# vusb_version.net
KiCad netlist of a schematic drawn in EAGLE
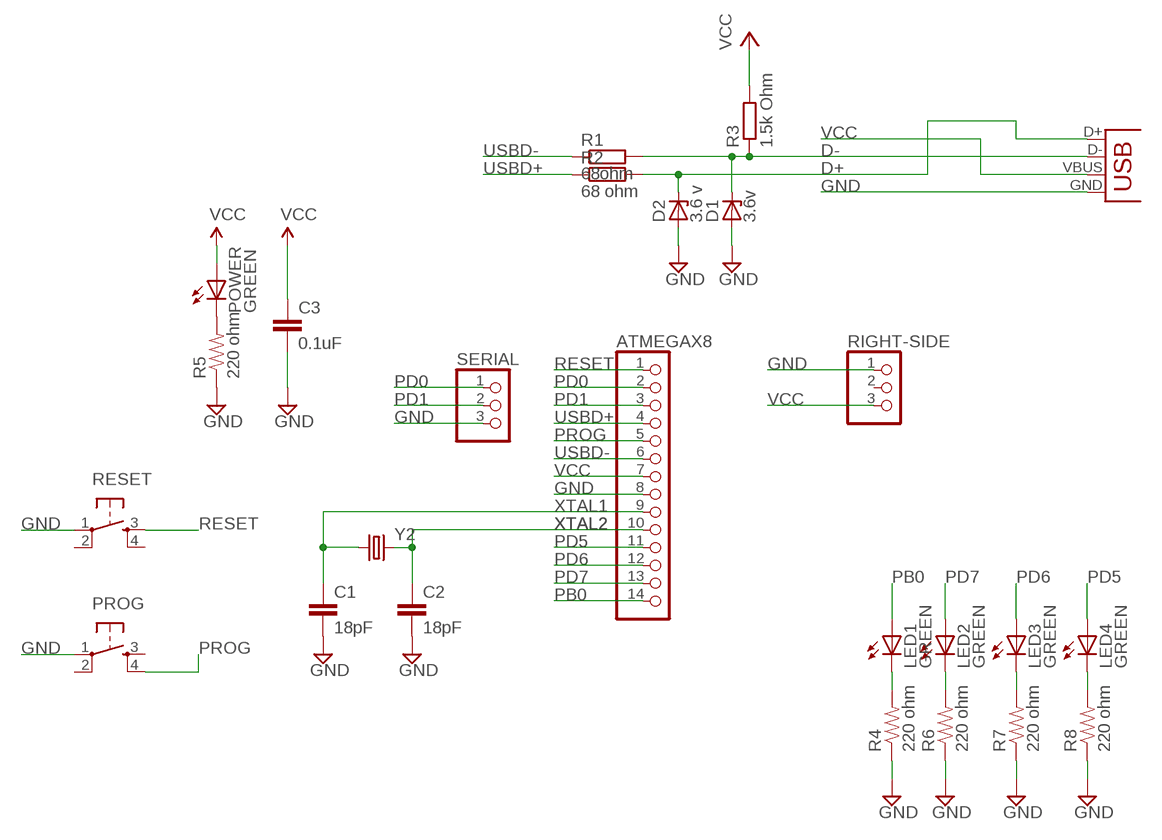
[diagram p0: schematic, sheet 1]

(export (version "E")
  (design (tool "Eeschema 10.0.6"))
  (components
    (comp (ref "ATMEGAX8")
      (value "PINHD-1X14")
      (footprint "eagle-import:1X14")
      (libsource (lib "eagle-import") (part "PINHD-1X14"))
    )
    (comp (ref "C1")
      (value "18pF")
      (footprint "eagle-import:1206")
      (libsource (lib "eagle-import") (part "CAP1206"))
    )
    (comp (ref "C2")
      (value "18pF")
      (footprint "eagle-import:1206")
      (libsource (lib "eagle-import") (part "CAP1206"))
    )
    (comp (ref "C3")
      (value "0.1uF")
      (footprint "eagle-import:1206")
      (libsource (lib "eagle-import") (part "CAP1206"))
    )
    (comp (ref "D1")
      (value "3.6v")
      (footprint "eagle-import:SOT23")
      (libsource (lib "eagle-import") (part "ZENER-DIODESOT23"))
    )
    (comp (ref "D2")
      (value "3.6 v")
      (footprint "eagle-import:SOT23")
      (libsource (lib "eagle-import") (part "ZENER-DIODESOT23"))
    )
    (comp (ref "JP1")
      (value "USBSMD")
      (footprint "eagle-import:USB-MINIB")
      (libsource (lib "eagle-import") (part "USBSMD"))
    )
    (comp (ref "LED1")
      (value "GREEN")
      (footprint "eagle-import:LED-1206")
      (libsource (lib "eagle-import") (part "LED-GREENLARGE"))
    )
    (comp (ref "LED2")
      (value "GREEN")
      (footprint "eagle-import:LED-1206")
      (libsource (lib "eagle-import") (part "LED-GREENLARGE"))
    )
    (comp (ref "LED3")
      (value "GREEN")
      (footprint "eagle-import:LED-1206")
      (libsource (lib "eagle-import") (part "LED-GREENLARGE"))
    )
    (comp (ref "LED4")
      (value "GREEN")
      (footprint "eagle-import:LED-1206")
      (libsource (lib "eagle-import") (part "LED-GREENLARGE"))
    )
    (comp (ref "POWER")
      (value "GREEN")
      (footprint "eagle-import:LED-1206")
      (libsource (lib "eagle-import") (part "LED-GREENLARGE"))
    )
    (comp (ref "PROG")
      (value "TAC_SWITCHPTH")
      (footprint "eagle-import:TACTILE-PTH")
      (libsource (lib "eagle-import") (part "TAC_SWITCHPTH"))
    )
    (comp (ref "R1")
      (value "68ohm")
      (footprint "eagle-import:R0805")
      (libsource (lib "eagle-import") (part "R-EU_R0805"))
    )
    (comp (ref "R2")
      (value "68 ohm")
      (footprint "eagle-import:R0805")
      (libsource (lib "eagle-import") (part "R-EU_R0805"))
    )
    (comp (ref "R3")
      (value "1.5k Ohm")
      (footprint "eagle-import:R1206")
      (libsource (lib "eagle-import") (part "R-EU_R1206"))
    )
    (comp (ref "R4")
      (value "220 ohm")
      (footprint "eagle-import:1206")
      (libsource (lib "eagle-import") (part "RESISTOR1206"))
    )
    (comp (ref "R5")
      (value "220 ohm")
      (footprint "eagle-import:1206")
      (libsource (lib "eagle-import") (part "RESISTOR1206"))
    )
    (comp (ref "R6")
      (value "220 ohm")
      (footprint "eagle-import:1206")
      (libsource (lib "eagle-import") (part "RESISTOR1206"))
    )
    (comp (ref "R7")
      (value "220 ohm")
      (footprint "eagle-import:1206")
      (libsource (lib "eagle-import") (part "RESISTOR1206"))
    )
    (comp (ref "R8")
      (value "220 ohm")
      (footprint "eagle-import:1206")
      (libsource (lib "eagle-import") (part "RESISTOR1206"))
    )
    (comp (ref "RESET")
      (value "TAC_SWITCHPTH")
      (footprint "eagle-import:TACTILE-PTH")
      (libsource (lib "eagle-import") (part "TAC_SWITCHPTH"))
    )
    (comp (ref "RIGHT-SIDE")
      (value "PINHD-1X3")
      (footprint "eagle-import:1X03")
      (libsource (lib "eagle-import") (part "PINHD-1X3"))
    )
    (comp (ref "SERIAL")
      (value "PINHD-1X3")
      (footprint "eagle-import:1X03")
      (libsource (lib "eagle-import") (part "PINHD-1X3"))
    )
    (comp (ref "Y2")
      (value "CRYSTALHC49US")
      (footprint "eagle-import:HC49US")
      (libsource (lib "eagle-import") (part "CRYSTALHC49US"))
    )
  )
  (nets
    (net (code "1") (name "/D+") (class "Default")
      (node (ref "D2") (pin "3") (pinfunction "C_3") (pintype "passive"))
      (node (ref "JP1") (pin "D+") (pinfunction "D+_D+") (pintype "bidirectional"))
      (node (ref "R2") (pin "2") (pinfunction "2_2") (pintype "passive"))
    )
    (net (code "2") (name "/D-") (class "Default")
      (node (ref "D1") (pin "3") (pinfunction "C_3") (pintype "passive"))
      (node (ref "JP1") (pin "D-") (pinfunction "D-_D-") (pintype "bidirectional"))
      (node (ref "R1") (pin "2") (pinfunction "2_2") (pintype "passive"))
      (node (ref "R3") (pin "1") (pinfunction "1_1") (pintype "passive"))
    )
    (net (code "3") (name "/PB0") (class "Default")
      (node (ref "LED1") (pin "A") (pinfunction "A_A") (pintype "passive"))
    )
    (net (code "4") (name "/PD0") (class "Default")
      (node (ref "ATMEGAX8") (pin "2") (pinfunction "2_2") (pintype "passive"))
      (node (ref "SERIAL") (pin "1") (pinfunction "1_1") (pintype "passive"))
    )
    (net (code "5") (name "/PD1") (class "Default")
      (node (ref "ATMEGAX8") (pin "3") (pinfunction "3_3") (pintype "passive"))
      (node (ref "SERIAL") (pin "2") (pinfunction "2_2") (pintype "passive"))
    )
    (net (code "6") (name "/PD5") (class "Default")
      (node (ref "ATMEGAX8") (pin "11") (pinfunction "11_11") (pintype "passive"))
      (node (ref "LED4") (pin "A") (pinfunction "A_A") (pintype "passive"))
    )
    (net (code "7") (name "/PD6") (class "Default")
      (node (ref "ATMEGAX8") (pin "12") (pinfunction "12_12") (pintype "passive"))
      (node (ref "LED3") (pin "A") (pinfunction "A_A") (pintype "passive"))
    )
    (net (code "8") (name "/PD7") (class "Default")
      (node (ref "ATMEGAX8") (pin "13") (pinfunction "13_13") (pintype "passive"))
      (node (ref "LED2") (pin "A") (pinfunction "A_A") (pintype "passive"))
    )
    (net (code "9") (name "/PROG") (class "Default")
      (node (ref "ATMEGAX8") (pin "5") (pinfunction "5_5") (pintype "passive"))
      (node (ref "PROG") (pin "4") (pinfunction "4_4") (pintype "passive"))
    )
    (net (code "10") (name "/RESET") (class "Default")
      (node (ref "ATMEGAX8") (pin "1") (pinfunction "1_1") (pintype "passive"))
      (node (ref "RESET") (pin "3") (pinfunction "3_3") (pintype "passive"))
    )
    (net (code "11") (name "/USBD+") (class "Default")
      (node (ref "ATMEGAX8") (pin "4") (pinfunction "4_4") (pintype "passive"))
      (node (ref "R2") (pin "1") (pinfunction "1_1") (pintype "passive"))
    )
    (net (code "12") (name "/USBD-") (class "Default")
      (node (ref "ATMEGAX8") (pin "6") (pinfunction "6_6") (pintype "passive"))
      (node (ref "R1") (pin "1") (pinfunction "1_1") (pintype "passive"))
    )
    (net (code "13") (name "/XTAL1") (class "Default")
      (node (ref "ATMEGAX8") (pin "9") (pinfunction "9_9") (pintype "passive"))
      (node (ref "C1") (pin "1") (pinfunction "1_1") (pintype "passive"))
      (node (ref "Y2") (pin "1") (pinfunction "1_1") (pintype "passive"))
    )
    (net (code "14") (name "/XTAL2") (class "Default")
      (node (ref "ATMEGAX8") (pin "10") (pinfunction "10_10") (pintype "passive"))
      (node (ref "C2") (pin "1") (pinfunction "1_1") (pintype "passive"))
      (node (ref "Y2") (pin "2") (pinfunction "2_2") (pintype "passive"))
    )
    (net (code "15") (name "GND") (class "Default")
      (node (ref "ATMEGAX8") (pin "8") (pinfunction "8_8") (pintype "passive"))
      (node (ref "C1") (pin "2") (pinfunction "2_2") (pintype "passive"))
      (node (ref "C2") (pin "2") (pinfunction "2_2") (pintype "passive"))
      (node (ref "C3") (pin "2") (pinfunction "2_2") (pintype "passive"))
      (node (ref "D1") (pin "1") (pinfunction "A_1") (pintype "passive"))
      (node (ref "D2") (pin "1") (pinfunction "A_1") (pintype "passive"))
      (node (ref "JP1") (pin "GND") (pinfunction "GND_GND") (pintype "bidirectional"))
      (node (ref "PROG") (pin "1") (pinfunction "1_1") (pintype "passive"))
      (node (ref "R4") (pin "1") (pinfunction "1_1") (pintype "passive"))
      (node (ref "R5") (pin "1") (pinfunction "1_1") (pintype "passive"))
      (node (ref "R6") (pin "1") (pinfunction "1_1") (pintype "passive"))
      (node (ref "R7") (pin "1") (pinfunction "1_1") (pintype "passive"))
      (node (ref "R8") (pin "1") (pinfunction "1_1") (pintype "passive"))
      (node (ref "RESET") (pin "1") (pinfunction "1_1") (pintype "passive"))
      (node (ref "RIGHT-SIDE") (pin "1") (pinfunction "1_1") (pintype "passive"))
      (node (ref "SERIAL") (pin "3") (pinfunction "3_3") (pintype "passive"))
    )
    (net (code "16") (name "Net-(LED1-PadC)") (class "Default")
      (node (ref "LED1") (pin "C") (pinfunction "C_C") (pintype "passive"))
      (node (ref "R4") (pin "2") (pinfunction "2_2") (pintype "passive"))
    )
    (net (code "17") (name "Net-(LED2-PadC)") (class "Default")
      (node (ref "LED2") (pin "C") (pinfunction "C_C") (pintype "passive"))
      (node (ref "R6") (pin "2") (pinfunction "2_2") (pintype "passive"))
    )
    (net (code "18") (name "Net-(LED3-PadC)") (class "Default")
      (node (ref "LED3") (pin "C") (pinfunction "C_C") (pintype "passive"))
      (node (ref "R7") (pin "2") (pinfunction "2_2") (pintype "passive"))
    )
    (net (code "19") (name "Net-(LED4-PadC)") (class "Default")
      (node (ref "LED4") (pin "C") (pinfunction "C_C") (pintype "passive"))
      (node (ref "R8") (pin "2") (pinfunction "2_2") (pintype "passive"))
    )
    (net (code "20") (name "Net-(POWER-PadC)") (class "Default")
      (node (ref "POWER") (pin "C") (pinfunction "C_C") (pintype "passive"))
      (node (ref "R5") (pin "2") (pinfunction "2_2") (pintype "passive"))
    )
    (net (code "21") (name "VCC") (class "Default")
      (node (ref "ATMEGAX8") (pin "7") (pinfunction "7_7") (pintype "passive"))
      (node (ref "C3") (pin "1") (pinfunction "1_1") (pintype "passive"))
      (node (ref "JP1") (pin "VBUS") (pinfunction "VBUS_VBUS") (pintype "bidirectional"))
      (node (ref "POWER") (pin "A") (pinfunction "A_A") (pintype "passive"))
      (node (ref "R3") (pin "2") (pinfunction "2_2") (pintype "passive"))
      (node (ref "RIGHT-SIDE") (pin "3") (pinfunction "3_3") (pintype "passive"))
    )
    (net (code "22") (name "unconnected-(ATMEGAX8-Pad14)") (class "Default")
      (node (ref "ATMEGAX8") (pin "14") (pinfunction "14_14") (pintype "passive"))
    )
    (net (code "23") (name "unconnected-(PROG-Pad2)") (class "Default")
      (node (ref "PROG") (pin "2") (pinfunction "2_2") (pintype "passive"))
    )
    (net (code "24") (name "unconnected-(PROG-Pad3)") (class "Default")
      (node (ref "PROG") (pin "3") (pinfunction "3_3") (pintype "passive"))
    )
    (net (code "25") (name "unconnected-(RESET-Pad2)") (class "Default")
      (node (ref "RESET") (pin "2") (pinfunction "2_2") (pintype "passive"))
    )
    (net (code "26") (name "unconnected-(RESET-Pad4)") (class "Default")
      (node (ref "RESET") (pin "4") (pinfunction "4_4") (pintype "passive"))
    )
    (net (code "27") (name "unconnected-(RIGHT-SIDE-Pad2)") (class "Default")
      (node (ref "RIGHT-SIDE") (pin "2") (pinfunction "2_2") (pintype "passive"))
    )
  )
)
